# ESP32_Wroom_Design.net
KiCad netlist of a schematic drawn in Altium Designer
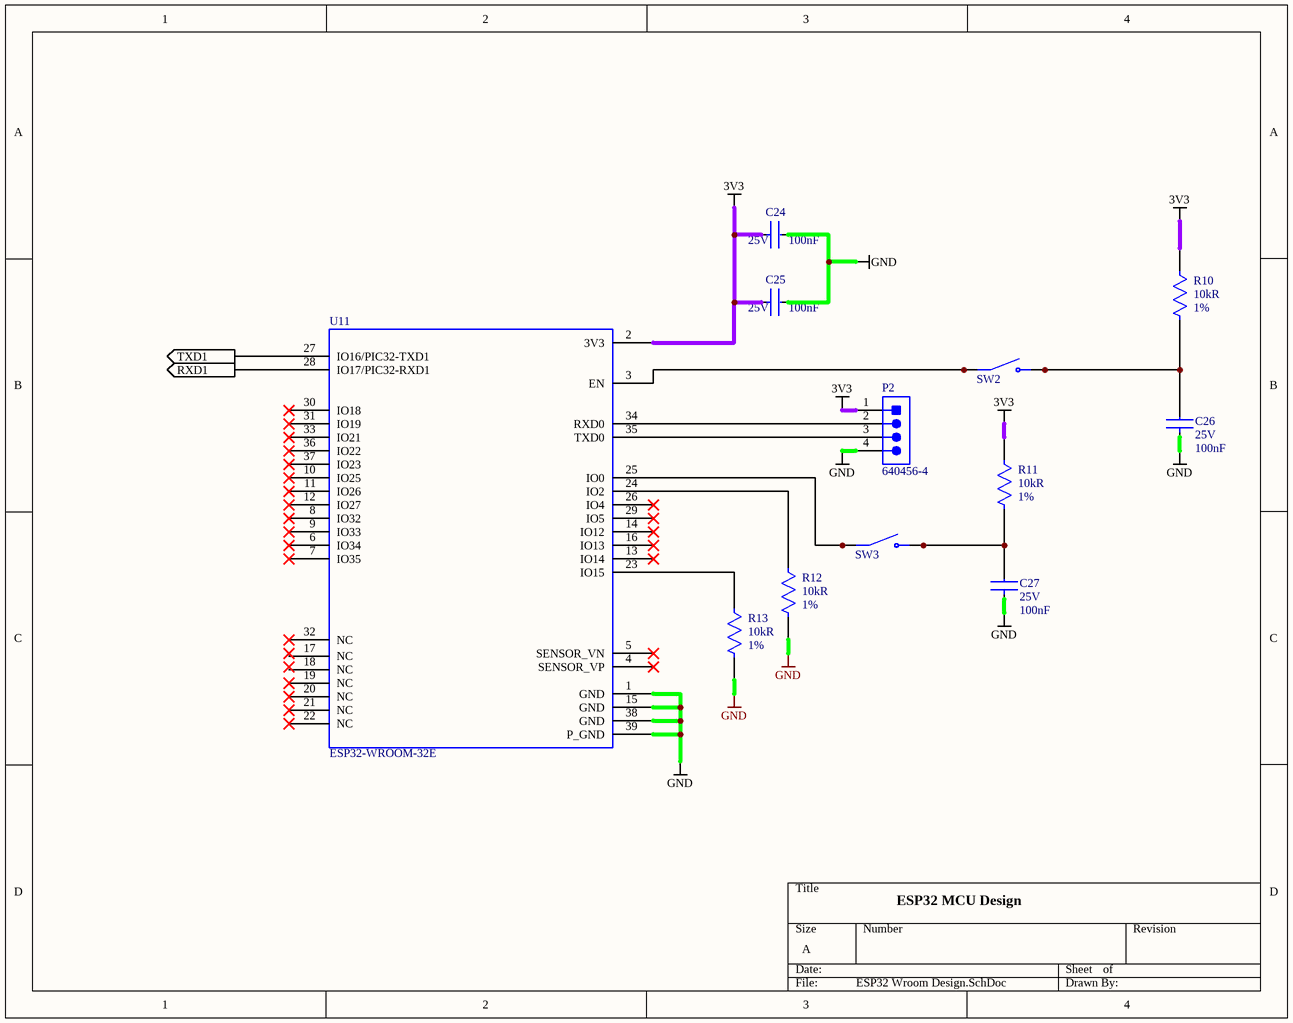
[diagram p0: ESP32 Wroom Design.SchDoc]

(export (version "E")
  (design (tool "Eeschema 10.0.6"))
  (components
    (comp (ref "C24")
      (value "~")
      (footprint "FP-CL278-IPC_C")
      (description "Cap Ceramic 100nF 25V X5R ±10% SMD 0402 +85°C Paper T/R")
      (fields
        (field (name "VOLTAGE") "25V")
        (field (name "TOLERANCE") "10%")
        (field (name "CAPACITANCE") "100nF")
      )
      (libsource (lib "Altium Content Vault") (part "b4654b650e69147ec39a6b967a45e02"))
    )
    (comp (ref "C25")
      (value "~")
      (footprint "FP-CL278-IPC_C")
      (description "Cap Ceramic 100nF 25V X5R ±10% SMD 0402 +85°C Paper T/R")
      (fields
        (field (name "VOLTAGE") "25V")
        (field (name "TOLERANCE") "10%")
        (field (name "CAPACITANCE") "100nF")
      )
      (libsource (lib "Altium Content Vault") (part "b4654b650e69147ec39a6b967a45e02"))
    )
    (comp (ref "C26")
      (value "~")
      (footprint "FP-CL278-IPC_C")
      (description "Cap Ceramic 100nF 25V X5R ±10% SMD 0402 +85°C Paper T/R")
      (fields
        (field (name "VOLTAGE") "25V")
        (field (name "TOLERANCE") "10%")
        (field (name "CAPACITANCE") "100nF")
      )
      (libsource (lib "Altium Content Vault") (part "b4654b650e69147ec39a6b967a45e02"))
    )
    (comp (ref "C27")
      (value "~")
      (footprint "FP-CL278-IPC_C")
      (description "Cap Ceramic 100nF 25V X5R ±10% SMD 0402 +85°C Paper T/R")
      (fields
        (field (name "VOLTAGE") "25V")
        (field (name "TOLERANCE") "10%")
        (field (name "CAPACITANCE") "100nF")
      )
      (libsource (lib "Altium Content Vault") (part "b4654b650e69147ec39a6b967a45e02"))
    )
    (comp (ref "P2")
      (value "640456-4")
      (footprint "TECO-640456-4")
      (description "Male Header, Pitch 2.54 mm, 1 x 4 Position, Height 10.03 mm, Tail Length 3.56 mm, RoHS, Bulk")
      (fields (field (name "MANUFACTURER") "TE Connectivity"))
      (libsource (lib "Altium Content Vault") (part "CN-1P-M-R4"))
    )
    (comp (ref "R10")
      (value "RMCF0201FT10K0")
      (footprint "FP-RMCF0201-IPC_B")
      (description "RES 10K OHM 1% 1/20W 0201")
      (fields (field (name "RESISTANCE") "10kR") (field (name "TOLERANCE") "1%"))
      (libsource (lib "Altium Content Vault") (part "1029c3af85768c4190bb7ad29bc67b5"))
    )
    (comp (ref "R11")
      (value "RMCF0201FT10K0")
      (footprint "FP-RMCF0201-IPC_B")
      (description "RES 10K OHM 1% 1/20W 0201")
      (fields (field (name "RESISTANCE") "10kR") (field (name "TOLERANCE") "1%"))
      (libsource (lib "Altium Content Vault") (part "1029c3af85768c4190bb7ad29bc67b5"))
    )
    (comp (ref "R12")
      (value "RMCF0201FT10K0")
      (footprint "FP-RMCF0201-IPC_B")
      (description "RES 10K OHM 1% 1/20W 0201")
      (fields (field (name "RESISTANCE") "10kR") (field (name "TOLERANCE") "1%"))
      (libsource (lib "Altium Content Vault") (part "1029c3af85768c4190bb7ad29bc67b5"))
    )
    (comp (ref "R13")
      (value "RMCF0201FT10K0")
      (footprint "FP-RMCF0201-IPC_B")
      (description "RES 10K OHM 1% 1/20W 0201")
      (fields (field (name "RESISTANCE") "10kR") (field (name "TOLERANCE") "1%"))
      (libsource (lib "Altium Content Vault") (part "1029c3af85768c4190bb7ad29bc67b5"))
    )
    (comp (ref "SW2")
      (value "401-1978-ND")
      (footprint "PushButtonSwitch")
      (libsource (lib "ECEN215LabKit_Library") (part "Push Button Switch"))
    )
    (comp (ref "SW3")
      (value "401-1978-ND")
      (footprint "PushButtonSwitch")
      (libsource (lib "ECEN215LabKit_Library") (part "Push Button Switch"))
    )
    (comp (ref "U11")
      (value "ESP32-WROOM-32E")
      (footprint "ESP32-Wroom-32E")
      (libsource (lib "ECEN215LabKit_Library") (part "ESP32-WROOM-32E"))
    )
  )
  (nets
    (net (code "1") (name "/RXD1") (class "Default")
      (node (ref "U11") (pin "28") (pinfunction "IO17/PIC32-RXD1_28") (pintype "passive"))
    )
    (net (code "2") (name "/TXD1") (class "Default")
      (node (ref "U11") (pin "27") (pinfunction "IO16/PIC32-TXD1_27") (pintype "passive"))
    )
    (net (code "3") (name "3V3") (class "Default")
      (node (ref "C24") (pin "1") (pinfunction "1_1") (pintype "passive"))
      (node (ref "C25") (pin "1") (pinfunction "1_1") (pintype "passive"))
      (node (ref "P2") (pin "1") (pinfunction "1_1") (pintype "passive"))
      (node (ref "R10") (pin "1") (pinfunction "1_1") (pintype "passive"))
      (node (ref "R11") (pin "1") (pinfunction "1_1") (pintype "passive"))
      (node (ref "U11") (pin "2") (pinfunction "3V3_2") (pintype "power_in"))
    )
    (net (code "4") (name "GND") (class "Default")
      (node (ref "C24") (pin "2") (pinfunction "2_2") (pintype "passive"))
      (node (ref "C25") (pin "2") (pinfunction "2_2") (pintype "passive"))
      (node (ref "C26") (pin "1") (pinfunction "1_1") (pintype "passive"))
      (node (ref "C27") (pin "1") (pinfunction "1_1") (pintype "passive"))
      (node (ref "P2") (pin "4") (pinfunction "4_4") (pintype "passive"))
      (node (ref "R12") (pin "2") (pinfunction "2_2") (pintype "passive"))
      (node (ref "R13") (pin "2") (pinfunction "2_2") (pintype "passive"))
      (node (ref "U11") (pin "1") (pinfunction "GND_1") (pintype "power_in"))
      (node (ref "U11") (pin "15") (pinfunction "GND_15") (pintype "power_in"))
      (node (ref "U11") (pin "38") (pinfunction "GND_38") (pintype "power_in"))
      (node (ref "U11") (pin "39") (pinfunction "P_GND_39") (pintype "power_in"))
    )
    (net (code "5") (name "Net-(C26-Pad2)") (class "Default")
      (node (ref "C26") (pin "2") (pinfunction "2_2") (pintype "passive"))
      (node (ref "R10") (pin "2") (pinfunction "2_2") (pintype "passive"))
      (node (ref "SW2") (pin "3") (pinfunction "NO_3") (pintype "passive"))
      (node (ref "SW2") (pin "4") (pinfunction "NO_4") (pintype "passive"))
    )
    (net (code "6") (name "Net-(C27-Pad2)") (class "Default")
      (node (ref "C27") (pin "2") (pinfunction "2_2") (pintype "passive"))
      (node (ref "R11") (pin "2") (pinfunction "2_2") (pintype "passive"))
      (node (ref "SW3") (pin "3") (pinfunction "NO_3") (pintype "passive"))
      (node (ref "SW3") (pin "4") (pinfunction "NO_4") (pintype "passive"))
    )
    (net (code "7") (name "Net-(U11-EN)") (class "Default")
      (node (ref "SW2") (pin "1") (pinfunction "COM_1") (pintype "passive"))
      (node (ref "SW2") (pin "2") (pinfunction "COM_2") (pintype "passive"))
      (node (ref "U11") (pin "3") (pinfunction "EN_3") (pintype "passive"))
    )
    (net (code "8") (name "Net-(U11-IO0)") (class "Default")
      (node (ref "SW3") (pin "1") (pinfunction "COM_1") (pintype "passive"))
      (node (ref "SW3") (pin "2") (pinfunction "COM_2") (pintype "passive"))
      (node (ref "U11") (pin "25") (pinfunction "IO0_25") (pintype "passive"))
    )
    (net (code "9") (name "Net-(U11-IO2)") (class "Default")
      (node (ref "R12") (pin "1") (pinfunction "1_1") (pintype "passive"))
      (node (ref "U11") (pin "24") (pinfunction "IO2_24") (pintype "passive"))
    )
    (net (code "10") (name "Net-(U11-IO15)") (class "Default")
      (node (ref "R13") (pin "1") (pinfunction "1_1") (pintype "passive"))
      (node (ref "U11") (pin "23") (pinfunction "IO15_23") (pintype "passive"))
    )
    (net (code "11") (name "Net-(U11-RXD0)") (class "Default")
      (node (ref "P2") (pin "2") (pinfunction "2_2") (pintype "passive"))
      (node (ref "U11") (pin "34") (pinfunction "RXD0_34") (pintype "passive"))
    )
    (net (code "12") (name "Net-(U11-TXD0)") (class "Default")
      (node (ref "P2") (pin "3") (pinfunction "3_3") (pintype "passive"))
      (node (ref "U11") (pin "35") (pinfunction "TXD0_35") (pintype "passive"))
    )
    (net (code "13") (name "unconnected-(U11-IO4-Pad26)") (class "Default")
      (node (ref "U11") (pin "26") (pinfunction "IO4_26") (pintype "passive+no_connect"))
    )
    (net (code "14") (name "unconnected-(U11-IO5-Pad29)") (class "Default")
      (node (ref "U11") (pin "29") (pinfunction "IO5_29") (pintype "passive+no_connect"))
    )
    (net (code "15") (name "unconnected-(U11-IO12-Pad14)") (class "Default")
      (node (ref "U11") (pin "14") (pinfunction "IO12_14") (pintype "passive+no_connect"))
    )
    (net (code "16") (name "unconnected-(U11-IO13-Pad16)") (class "Default")
      (node (ref "U11") (pin "16") (pinfunction "IO13_16") (pintype "passive+no_connect"))
    )
    (net (code "17") (name "unconnected-(U11-IO14-Pad13)") (class "Default")
      (node (ref "U11") (pin "13") (pinfunction "IO14_13") (pintype "passive+no_connect"))
    )
    (net (code "18") (name "unconnected-(U11-IO18-Pad30)") (class "Default")
      (node (ref "U11") (pin "30") (pinfunction "IO18_30") (pintype "passive+no_connect"))
    )
    (net (code "19") (name "unconnected-(U11-IO19-Pad31)") (class "Default")
      (node (ref "U11") (pin "31") (pinfunction "IO19_31") (pintype "passive+no_connect"))
    )
    (net (code "20") (name "unconnected-(U11-IO21-Pad33)") (class "Default")
      (node (ref "U11") (pin "33") (pinfunction "IO21_33") (pintype "passive+no_connect"))
    )
    (net (code "21") (name "unconnected-(U11-IO22-Pad36)") (class "Default")
      (node (ref "U11") (pin "36") (pinfunction "IO22_36") (pintype "passive+no_connect"))
    )
    (net (code "22") (name "unconnected-(U11-IO23-Pad37)") (class "Default")
      (node (ref "U11") (pin "37") (pinfunction "IO23_37") (pintype "passive+no_connect"))
    )
    (net (code "23") (name "unconnected-(U11-IO25-Pad10)") (class "Default")
      (node (ref "U11") (pin "10") (pinfunction "IO25_10") (pintype "passive+no_connect"))
    )
    (net (code "24") (name "unconnected-(U11-IO26-Pad11)") (class "Default")
      (node (ref "U11") (pin "11") (pinfunction "IO26_11") (pintype "passive+no_connect"))
    )
    (net (code "25") (name "unconnected-(U11-IO27-Pad12)") (class "Default")
      (node (ref "U11") (pin "12") (pinfunction "IO27_12") (pintype "passive+no_connect"))
    )
    (net (code "26") (name "unconnected-(U11-IO32-Pad8)") (class "Default")
      (node (ref "U11") (pin "8") (pinfunction "IO32_8") (pintype "passive+no_connect"))
    )
    (net (code "27") (name "unconnected-(U11-IO33-Pad9)") (class "Default")
      (node (ref "U11") (pin "9") (pinfunction "IO33_9") (pintype "passive+no_connect"))
    )
    (net (code "28") (name "unconnected-(U11-IO34-Pad6)") (class "Default")
      (node (ref "U11") (pin "6") (pinfunction "IO34_6") (pintype "passive+no_connect"))
    )
    (net (code "29") (name "unconnected-(U11-IO35-Pad7)") (class "Default")
      (node (ref "U11") (pin "7") (pinfunction "IO35_7") (pintype "passive+no_connect"))
    )
    (net (code "30") (name "unconnected-(U11-NC-Pad17)") (class "Default")
      (node (ref "U11") (pin "17") (pinfunction "NC_17") (pintype "passive"))
    )
    (net (code "31") (name "unconnected-(U11-NC-Pad18)") (class "Default")
      (node (ref "U11") (pin "18") (pinfunction "NC_18") (pintype "passive"))
    )
    (net (code "32") (name "unconnected-(U11-NC-Pad19)") (class "Default")
      (node (ref "U11") (pin "19") (pinfunction "NC_19") (pintype "passive+no_connect"))
    )
    (net (code "33") (name "unconnected-(U11-NC-Pad20)") (class "Default")
      (node (ref "U11") (pin "20") (pinfunction "NC_20") (pintype "passive+no_connect"))
    )
    (net (code "34") (name "unconnected-(U11-NC-Pad21)") (class "Default")
      (node (ref "U11") (pin "21") (pinfunction "NC_21") (pintype "passive+no_connect"))
    )
    (net (code "35") (name "unconnected-(U11-NC-Pad22)") (class "Default")
      (node (ref "U11") (pin "22") (pinfunction "NC_22") (pintype "passive+no_connect"))
    )
    (net (code "36") (name "unconnected-(U11-NC-Pad32)") (class "Default")
      (node (ref "U11") (pin "32") (pinfunction "NC_32") (pintype "passive+no_connect"))
    )
    (net (code "37") (name "unconnected-(U11-SENSOR_VN-Pad5)") (class "Default")
      (node (ref "U11") (pin "5") (pinfunction "SENSOR_VN_5") (pintype "passive+no_connect"))
    )
    (net (code "38") (name "unconnected-(U11-SENSOR_VP-Pad4)") (class "Default")
      (node (ref "U11") (pin "4") (pinfunction "SENSOR_VP_4") (pintype "passive+no_connect"))
    )
  )
)
